# Current_Mirror_2.net
KiCad netlist of a schematic drawn in Altium Designer
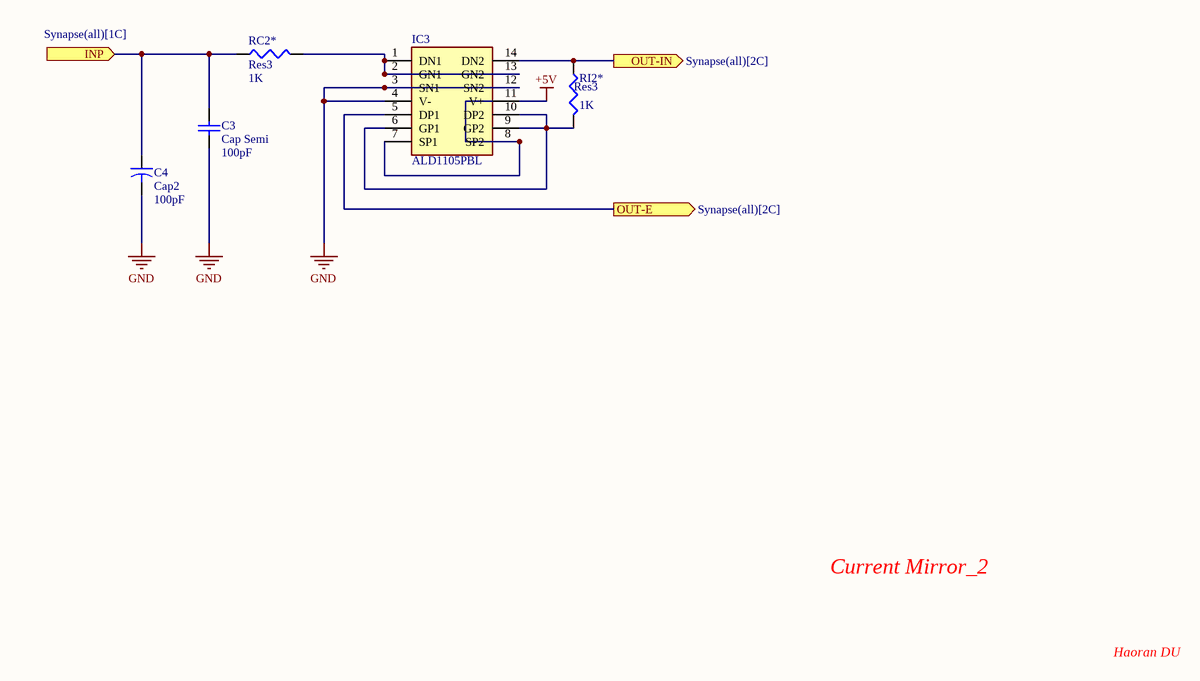
[diagram p0: Current Mirror_2.SchDoc]

(export (version "E")
  (design (tool "Eeschema 10.0.6"))
  (components
    (comp (ref "C3")
      (value "Cap Semi")
      (footprint "C1206")
      (description "Capacitor (Semiconductor SIM Model)")
      (fields (field (name "ALTIUM_VALUE") "100pF") (field (name "PUBLISHER") "Altium Limited"))
      (libsource (lib "Miscellaneous Devices") (part "Cap Semi"))
    )
    (comp (ref "C4")
      (value "Cap2")
      (footprint "CAPR5-4X5")
      (description "Capacitor")
      (fields (field (name "ALTIUM_VALUE") "100pF") (field (name "PUBLISHER") "Altium Limited"))
      (libsource (lib "Miscellaneous Devices") (part "Cap2"))
    )
    (comp (ref "IC3")
      (value "ALD1105PBL")
      (footprint "SamacSys:DIP762W51P254L1828H508Q14N")
      (description "Integrated Circuit")
      (fields (field (name "MOUSER PART NUMBER") "585-ALD1105PBL"))
      (libsource (lib "*") (part "ALD1105PBL"))
    )
    (comp (ref "RC2*")
      (value "Res3")
      (footprint "J1-0603")
      (description "Resistor")
      (fields (field (name "ALTIUM_VALUE") "1K") (field (name "PUBLISHER") "Altium Limited"))
      (libsource (lib "Miscellaneous Devices") (part "Res3"))
    )
    (comp (ref "RI2*")
      (value "Res3")
      (footprint "J1-0603")
      (description "Resistor")
      (fields (field (name "ALTIUM_VALUE") "1K") (field (name "PUBLISHER") "Altium Limited"))
      (libsource (lib "Miscellaneous Devices") (part "Res3"))
    )
  )
  (nets
    (net (code "1") (name "+5V") (class "Default")
      (node (ref "IC3") (pin "11") (pinfunction "V+_11") (pintype "passive"))
    )
    (net (code "2") (name "/INP") (class "Default")
      (node (ref "C3") (pin "2") (pinfunction "2_2") (pintype "passive"))
      (node (ref "C4") (pin "1") (pinfunction "1_1") (pintype "passive"))
      (node (ref "RC2*") (pin "1") (pinfunction "1_1") (pintype "passive"))
    )
    (net (code "3") (name "/OUT-E") (class "Default")
      (node (ref "IC3") (pin "5") (pinfunction "DP1_5") (pintype "passive"))
    )
    (net (code "4") (name "/OUT-IN") (class "Default")
      (node (ref "IC3") (pin "14") (pinfunction "DN2_14") (pintype "passive"))
      (node (ref "RI2*") (pin "1") (pinfunction "1_1") (pintype "passive"))
    )
    (net (code "5") (name "GND") (class "Default")
      (node (ref "C3") (pin "1") (pinfunction "1_1") (pintype "passive"))
      (node (ref "C4") (pin "2") (pinfunction "2_2") (pintype "passive"))
      (node (ref "IC3") (pin "12") (pinfunction "SN2_12") (pintype "passive"))
      (node (ref "IC3") (pin "3") (pinfunction "SN1_3") (pintype "passive"))
      (node (ref "IC3") (pin "4") (pinfunction "V-_4") (pintype "passive"))
    )
    (net (code "6") (name "Net-(IC3-DN1)") (class "Default")
      (node (ref "IC3") (pin "1") (pinfunction "DN1_1") (pintype "passive"))
      (node (ref "IC3") (pin "13") (pinfunction "GN2_13") (pintype "passive"))
      (node (ref "IC3") (pin "2") (pinfunction "GN1_2") (pintype "passive"))
      (node (ref "RC2*") (pin "2") (pinfunction "2_2") (pintype "passive"))
    )
    (net (code "7") (name "Net-(IC3-DP2)") (class "Default")
      (node (ref "IC3") (pin "10") (pinfunction "DP2_10") (pintype "passive"))
      (node (ref "IC3") (pin "6") (pinfunction "GP1_6") (pintype "passive"))
      (node (ref "IC3") (pin "9") (pinfunction "GP2_9") (pintype "passive"))
      (node (ref "RI2*") (pin "2") (pinfunction "2_2") (pintype "passive"))
    )
    (net (code "8") (name "Net-(IC3-SP1)") (class "Default")
      (node (ref "IC3") (pin "7") (pinfunction "SP1_7") (pintype "passive"))
      (node (ref "IC3") (pin "8") (pinfunction "SP2_8") (pintype "passive"))
    )
  )
)
